# robomow_usb.net
KiCad netlist of a schematic drawn in EAGLE
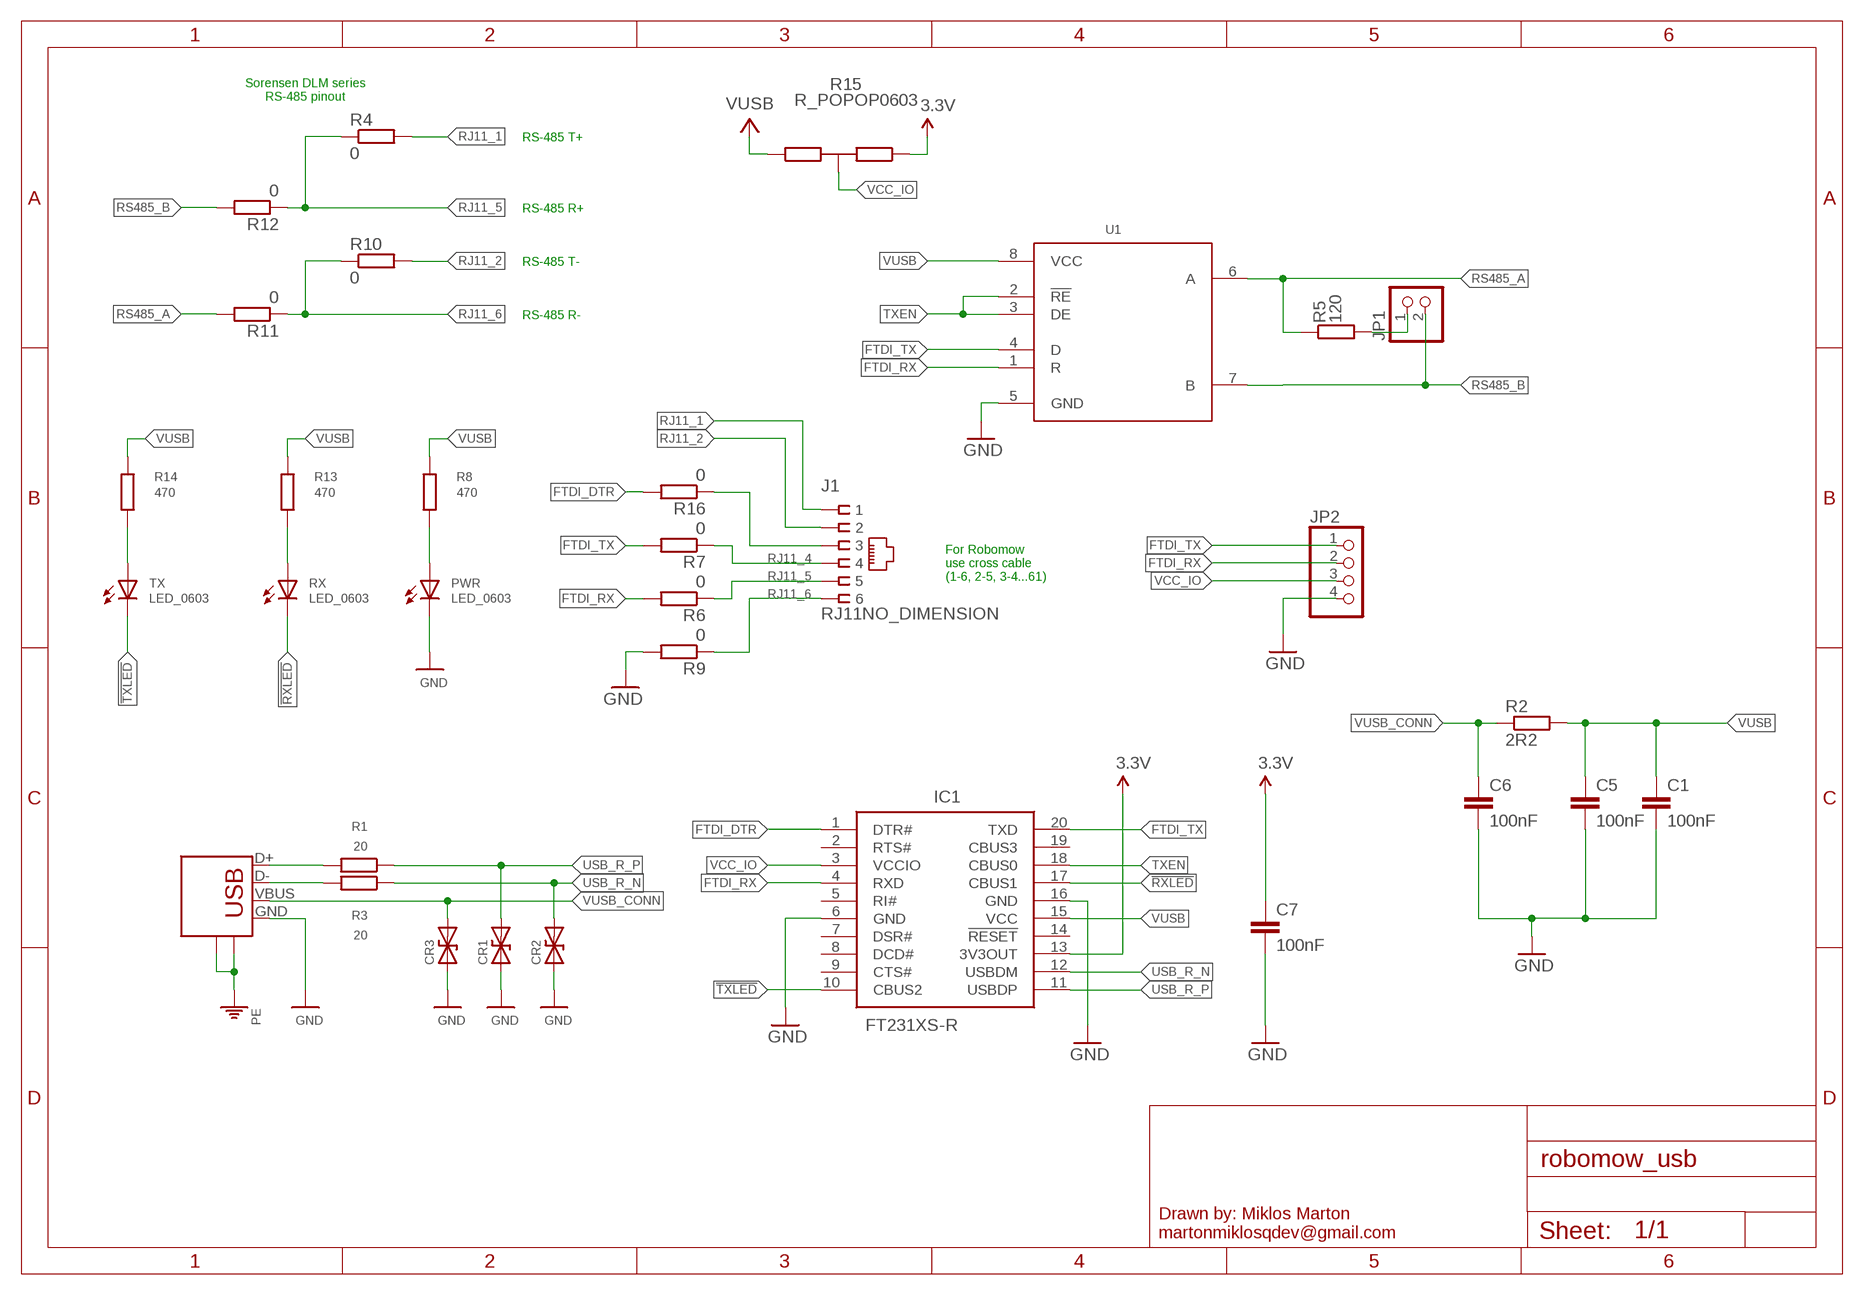
[diagram p0: schematic, sheet 1]

(export (version "E")
  (design (tool "Eeschema 10.0.6"))
  (components
    (comp (ref "C1")
      (value "100nF")
      (footprint "eagle-import:C0603")
      (libsource (lib "eagle-import") (part "C-EUC0603"))
    )
    (comp (ref "C5")
      (value "100nF")
      (footprint "eagle-import:C0603")
      (libsource (lib "eagle-import") (part "C-EUC0603"))
    )
    (comp (ref "C6")
      (value "100nF")
      (footprint "eagle-import:C0603")
      (libsource (lib "eagle-import") (part "C-EUC0603"))
    )
    (comp (ref "C7")
      (value "100nF")
      (footprint "eagle-import:C0603")
      (libsource (lib "eagle-import") (part "C-EUC0603"))
    )
    (comp (ref "CR1")
      (value "0603ESDA2-TR2")
      (footprint "eagle-import:0603")
      (libsource (lib "eagle-import") (part "0603ESDA2-TR2"))
    )
    (comp (ref "CR2")
      (value "0603ESDA2-TR2")
      (footprint "eagle-import:0603")
      (libsource (lib "eagle-import") (part "0603ESDA2-TR2"))
    )
    (comp (ref "CR3")
      (value "0603ESDA2-TR2")
      (footprint "eagle-import:0603")
      (libsource (lib "eagle-import") (part "0603ESDA2-TR2"))
    )
    (comp (ref "IC1")
      (value "FT231XS-R")
      (footprint "eagle-import:SOP64P599X175-20N")
      (fields (field (name "RS_PART_NUMBER") "7570032P"))
      (libsource (lib "eagle-import") (part "FT231XS-R"))
    )
    (comp (ref "J1")
      (value "RJ11NO_DIMENSION")
      (footprint "eagle-import:RJ11-NO_SHIELD_NO_DIMENSION")
      (libsource (lib "eagle-import") (part "RJ11NO_DIMENSION"))
    )
    (comp (ref "JP1")
      (value "PINHD-1X2")
      (footprint "eagle-import:1X02")
      (libsource (lib "eagle-import") (part "PINHD-1X2"))
    )
    (comp (ref "JP2")
      (value "PINHD-1X4")
      (footprint "eagle-import:1X04")
      (libsource (lib "eagle-import") (part "PINHD-1X4"))
    )
    (comp (ref "JUSB")
      (value "USBPTH")
      (footprint "eagle-import:USB-B-PTH")
      (libsource (lib "eagle-import") (part "USBPTH"))
    )
    (comp (ref "PWR")
      (value "LED_0603")
      (footprint "eagle-import:LED-603")
      (libsource (lib "eagle-import") (part "LED-0603"))
    )
    (comp (ref "R1")
      (value "20")
      (footprint "eagle-import:R0603")
      (libsource (lib "eagle-import") (part "R-EU_R0603"))
    )
    (comp (ref "R2")
      (value "2R2")
      (footprint "eagle-import:R0603")
      (libsource (lib "eagle-import") (part "R-EU_R0603"))
    )
    (comp (ref "R3")
      (value "20")
      (footprint "eagle-import:R0603")
      (libsource (lib "eagle-import") (part "R-EU_R0603"))
    )
    (comp (ref "R4")
      (value "0")
      (footprint "eagle-import:R0603")
      (libsource (lib "eagle-import") (part "R-EU_R0603"))
    )
    (comp (ref "R5")
      (value "120")
      (footprint "eagle-import:R0603")
      (libsource (lib "eagle-import") (part "R-EU_R0603"))
    )
    (comp (ref "R6")
      (value "0")
      (footprint "eagle-import:R0603")
      (libsource (lib "eagle-import") (part "R-EU_R0603"))
    )
    (comp (ref "R7")
      (value "0")
      (footprint "eagle-import:R0603")
      (libsource (lib "eagle-import") (part "R-EU_R0603"))
    )
    (comp (ref "R8")
      (value "470")
      (footprint "eagle-import:R0603")
      (libsource (lib "eagle-import") (part "R-EU_R0603"))
    )
    (comp (ref "R9")
      (value "0")
      (footprint "eagle-import:R0603")
      (libsource (lib "eagle-import") (part "R-EU_R0603"))
    )
    (comp (ref "R10")
      (value "0")
      (footprint "eagle-import:R0603")
      (libsource (lib "eagle-import") (part "R-EU_R0603"))
    )
    (comp (ref "R11")
      (value "0")
      (footprint "eagle-import:R0603")
      (libsource (lib "eagle-import") (part "R-EU_R0603"))
    )
    (comp (ref "R12")
      (value "0")
      (footprint "eagle-import:R0603")
      (libsource (lib "eagle-import") (part "R-EU_R0603"))
    )
    (comp (ref "R13")
      (value "470")
      (footprint "eagle-import:R0603")
      (libsource (lib "eagle-import") (part "R-EU_R0603"))
    )
    (comp (ref "R14")
      (value "470")
      (footprint "eagle-import:R0603")
      (libsource (lib "eagle-import") (part "R-EU_R0603"))
    )
    (comp (ref "R15")
      (value "R_POPOP0603")
      (footprint "eagle-import:0603_POPOP")
      (libsource (lib "eagle-import") (part "R_POPOP0603"))
    )
    (comp (ref "R16")
      (value "0")
      (footprint "eagle-import:R0603")
      (libsource (lib "eagle-import") (part "R-EU_R0603"))
    )
    (comp (ref "RX")
      (value "LED_0603")
      (footprint "eagle-import:LED-603")
      (libsource (lib "eagle-import") (part "LED-0603"))
    )
    (comp (ref "TX")
      (value "LED_0603")
      (footprint "eagle-import:LED-603")
      (libsource (lib "eagle-import") (part "LED-0603"))
    )
    (comp (ref "U1")
      (value "SN65HVD1176")
      (footprint "eagle-import:D0008A_N")
      (fields (field (name "MANUFACTURER") "Texas Instruments") (field (name "PARTNUMBER") "SN65HVD1176DR"))
      (libsource (lib "eagle-import") (part "SN65HVD1176DR"))
    )
  )
  (nets
    (net (code "1") (name "/RJ11_4") (class "Default")
      (node (ref "J1") (pin "4") (pinfunction "4_4") (pintype "passive"))
      (node (ref "R7") (pin "1") (pinfunction "1_1") (pintype "passive"))
    )
    (net (code "2") (name "/~{RXLED}") (class "Default")
      (node (ref "IC1") (pin "17") (pinfunction "CBUS1_17") (pintype "bidirectional"))
      (node (ref "RX") (pin "C") (pinfunction "C_C") (pintype "passive"))
    )
    (net (code "3") (name "/~{TXLED}") (class "Default")
      (node (ref "IC1") (pin "10") (pinfunction "CBUS2_10") (pintype "bidirectional"))
      (node (ref "TX") (pin "C") (pinfunction "C_C") (pintype "passive"))
    )
    (net (code "4") (name "3.3V") (class "Default")
      (node (ref "C7") (pin "1") (pinfunction "1_1") (pintype "passive"))
      (node (ref "IC1") (pin "13") (pinfunction "3V3OUT_13") (pintype "output"))
      (node (ref "R15") (pin "A") (pinfunction "A_A") (pintype "passive"))
    )
    (net (code "5") (name "FTDI_DTR") (class "Default")
      (node (ref "IC1") (pin "1") (pinfunction "DTR#_1") (pintype "bidirectional"))
      (node (ref "R16") (pin "2") (pinfunction "2_2") (pintype "passive"))
    )
    (net (code "6") (name "FTDI_RX") (class "Default")
      (node (ref "IC1") (pin "4") (pinfunction "RXD_4") (pintype "bidirectional"))
      (node (ref "JP2") (pin "2") (pinfunction "2_2") (pintype "passive"))
      (node (ref "R6") (pin "2") (pinfunction "2_2") (pintype "passive"))
      (node (ref "U1") (pin "1") (pinfunction "R_1") (pintype "output"))
    )
    (net (code "7") (name "FTDI_TX") (class "Default")
      (node (ref "IC1") (pin "20") (pinfunction "TXD_20") (pintype "bidirectional"))
      (node (ref "JP2") (pin "1") (pinfunction "1_1") (pintype "passive"))
      (node (ref "R7") (pin "2") (pinfunction "2_2") (pintype "passive"))
      (node (ref "U1") (pin "4") (pinfunction "D_4") (pintype "input"))
    )
    (net (code "8") (name "GND") (class "Default")
      (node (ref "C1") (pin "2") (pinfunction "2_2") (pintype "passive"))
      (node (ref "C5") (pin "2") (pinfunction "2_2") (pintype "passive"))
      (node (ref "C6") (pin "2") (pinfunction "2_2") (pintype "passive"))
      (node (ref "C7") (pin "2") (pinfunction "2_2") (pintype "passive"))
      (node (ref "CR1") (pin "1") (pinfunction "1_1") (pintype "passive"))
      (node (ref "CR2") (pin "1") (pinfunction "1_1") (pintype "passive"))
      (node (ref "CR3") (pin "1") (pinfunction "1_1") (pintype "passive"))
      (node (ref "IC1") (pin "16") (pinfunction "GND_16") (pintype "power_in"))
      (node (ref "IC1") (pin "6") (pinfunction "GND_6") (pintype "power_in"))
      (node (ref "JP2") (pin "4") (pinfunction "4_4") (pintype "passive"))
      (node (ref "JUSB") (pin "GND") (pinfunction "GND_GND") (pintype "bidirectional"))
      (node (ref "PWR") (pin "C") (pinfunction "C_C") (pintype "passive"))
      (node (ref "R9") (pin "2") (pinfunction "2_2") (pintype "passive"))
      (node (ref "U1") (pin "5") (pinfunction "GND_5") (pintype "power_in"))
    )
    (net (code "9") (name "Net-(J1-Pad3)") (class "Default")
      (node (ref "J1") (pin "3") (pinfunction "3_3") (pintype "passive"))
      (node (ref "R16") (pin "1") (pinfunction "1_1") (pintype "passive"))
    )
    (net (code "10") (name "Net-(JP1-Pad1)") (class "Default")
      (node (ref "JP1") (pin "1") (pinfunction "1_1") (pintype "passive"))
      (node (ref "R5") (pin "2") (pinfunction "2_2") (pintype "passive"))
    )
    (net (code "11") (name "Net-(JUSB-PadD+)") (class "Default")
      (node (ref "JUSB") (pin "D+") (pinfunction "D+_D+") (pintype "bidirectional"))
      (node (ref "R1") (pin "2") (pinfunction "2_2") (pintype "passive"))
    )
    (net (code "12") (name "Net-(JUSB-PadD-)") (class "Default")
      (node (ref "JUSB") (pin "D-") (pinfunction "D-_D-") (pintype "bidirectional"))
      (node (ref "R3") (pin "2") (pinfunction "2_2") (pintype "passive"))
    )
    (net (code "13") (name "Net-(PWR-PadA)") (class "Default")
      (node (ref "PWR") (pin "A") (pinfunction "A_A") (pintype "passive"))
      (node (ref "R8") (pin "2") (pinfunction "2_2") (pintype "passive"))
    )
    (net (code "14") (name "Net-(R13-Pad2)") (class "Default")
      (node (ref "R13") (pin "2") (pinfunction "2_2") (pintype "passive"))
      (node (ref "RX") (pin "A") (pinfunction "A_A") (pintype "passive"))
    )
    (net (code "15") (name "Net-(R14-Pad2)") (class "Default")
      (node (ref "R14") (pin "2") (pinfunction "2_2") (pintype "passive"))
      (node (ref "TX") (pin "A") (pinfunction "A_A") (pintype "passive"))
    )
    (net (code "16") (name "PE") (class "Default")
      (node (ref "JUSB") (pin "P$1") (pinfunction "SH1_P$1") (pintype "passive"))
      (node (ref "JUSB") (pin "P$2") (pinfunction "SH2_P$2") (pintype "passive"))
    )
    (net (code "17") (name "RJ11_1") (class "Default")
      (node (ref "J1") (pin "1") (pinfunction "1_1") (pintype "passive"))
      (node (ref "R4") (pin "2") (pinfunction "2_2") (pintype "passive"))
    )
    (net (code "18") (name "RJ11_2") (class "Default")
      (node (ref "J1") (pin "2") (pinfunction "2_2") (pintype "passive"))
      (node (ref "R10") (pin "2") (pinfunction "2_2") (pintype "passive"))
    )
    (net (code "19") (name "RJ11_5") (class "Default")
      (node (ref "J1") (pin "5") (pinfunction "5_5") (pintype "passive"))
      (node (ref "R12") (pin "1") (pinfunction "1_1") (pintype "passive"))
      (node (ref "R4") (pin "1") (pinfunction "1_1") (pintype "passive"))
      (node (ref "R6") (pin "1") (pinfunction "1_1") (pintype "passive"))
    )
    (net (code "20") (name "RJ11_6") (class "Default")
      (node (ref "J1") (pin "6") (pinfunction "6_6") (pintype "passive"))
      (node (ref "R10") (pin "1") (pinfunction "1_1") (pintype "passive"))
      (node (ref "R11") (pin "1") (pinfunction "1_1") (pintype "passive"))
      (node (ref "R9") (pin "1") (pinfunction "1_1") (pintype "passive"))
    )
    (net (code "21") (name "RS485_A") (class "Default")
      (node (ref "R11") (pin "2") (pinfunction "2_2") (pintype "passive"))
      (node (ref "R5") (pin "1") (pinfunction "1_1") (pintype "passive"))
      (node (ref "U1") (pin "6") (pinfunction "A_6") (pintype "bidirectional"))
    )
    (net (code "22") (name "RS485_B") (class "Default")
      (node (ref "JP1") (pin "2") (pinfunction "2_2") (pintype "passive"))
      (node (ref "R12") (pin "2") (pinfunction "2_2") (pintype "passive"))
      (node (ref "U1") (pin "7") (pinfunction "B_7") (pintype "bidirectional"))
    )
    (net (code "23") (name "TXEN") (class "Default")
      (node (ref "IC1") (pin "18") (pinfunction "CBUS0_18") (pintype "bidirectional"))
      (node (ref "U1") (pin "2") (pinfunction "~{RE}_2") (pintype "input"))
      (node (ref "U1") (pin "3") (pinfunction "DE_3") (pintype "input"))
    )
    (net (code "24") (name "USB_R_N") (class "Default")
      (node (ref "CR2") (pin "2") (pinfunction "2_2") (pintype "passive"))
      (node (ref "IC1") (pin "12") (pinfunction "USBDM_12") (pintype "bidirectional"))
      (node (ref "R3") (pin "1") (pinfunction "1_1") (pintype "passive"))
    )
    (net (code "25") (name "USB_R_P") (class "Default")
      (node (ref "CR1") (pin "2") (pinfunction "2_2") (pintype "passive"))
      (node (ref "IC1") (pin "11") (pinfunction "USBDP_11") (pintype "bidirectional"))
      (node (ref "R1") (pin "1") (pinfunction "1_1") (pintype "passive"))
    )
    (net (code "26") (name "VCC_IO") (class "Default")
      (node (ref "IC1") (pin "3") (pinfunction "VCCIO_3") (pintype "power_in"))
      (node (ref "JP2") (pin "3") (pinfunction "3_3") (pintype "passive"))
      (node (ref "R15") (pin "COM") (pinfunction "COM_COM") (pintype "passive"))
    )
    (net (code "27") (name "VUSB") (class "Default")
      (node (ref "C1") (pin "1") (pinfunction "1_1") (pintype "passive"))
      (node (ref "C5") (pin "1") (pinfunction "1_1") (pintype "passive"))
      (node (ref "IC1") (pin "15") (pinfunction "VCC_15") (pintype "power_in"))
      (node (ref "R13") (pin "1") (pinfunction "1_1") (pintype "passive"))
      (node (ref "R14") (pin "1") (pinfunction "1_1") (pintype "passive"))
      (node (ref "R15") (pin "A1") (pinfunction "B_A1") (pintype "passive"))
      (node (ref "R2") (pin "2") (pinfunction "2_2") (pintype "passive"))
      (node (ref "R8") (pin "1") (pinfunction "1_1") (pintype "passive"))
      (node (ref "U1") (pin "8") (pinfunction "VCC_8") (pintype "power_in"))
    )
    (net (code "28") (name "VUSB_CONN") (class "Default")
      (node (ref "C6") (pin "1") (pinfunction "1_1") (pintype "passive"))
      (node (ref "CR3") (pin "2") (pinfunction "2_2") (pintype "passive"))
      (node (ref "JUSB") (pin "VBUS") (pinfunction "VBUS_VBUS") (pintype "bidirectional"))
      (node (ref "R2") (pin "1") (pinfunction "1_1") (pintype "passive"))
    )
    (net (code "29") (name "unconnected-(IC1-CBUS3-Pad19)") (class "Default")
      (node (ref "IC1") (pin "19") (pinfunction "CBUS3_19") (pintype "bidirectional"))
    )
    (net (code "30") (name "unconnected-(IC1-CTS#-Pad9)") (class "Default")
      (node (ref "IC1") (pin "9") (pinfunction "CTS#_9") (pintype "bidirectional"))
    )
    (net (code "31") (name "unconnected-(IC1-DCD#-Pad8)") (class "Default")
      (node (ref "IC1") (pin "8") (pinfunction "DCD#_8") (pintype "bidirectional"))
    )
    (net (code "32") (name "unconnected-(IC1-DSR#-Pad7)") (class "Default")
      (node (ref "IC1") (pin "7") (pinfunction "DSR#_7") (pintype "bidirectional"))
    )
    (net (code "33") (name "unconnected-(IC1-RI#-Pad5)") (class "Default")
      (node (ref "IC1") (pin "5") (pinfunction "RI#_5") (pintype "bidirectional"))
    )
    (net (code "34") (name "unconnected-(IC1-RTS#-Pad2)") (class "Default")
      (node (ref "IC1") (pin "2") (pinfunction "RTS#_2") (pintype "bidirectional"))
    )
    (net (code "35") (name "unconnected-(IC1-~{RESET}-Pad14)") (class "Default")
      (node (ref "IC1") (pin "14") (pinfunction "~{RESET}_14") (pintype "bidirectional"))
    )
  )
)
